# Subsheet_CAN.net
KiCad netlist of a schematic drawn in Altium Designer
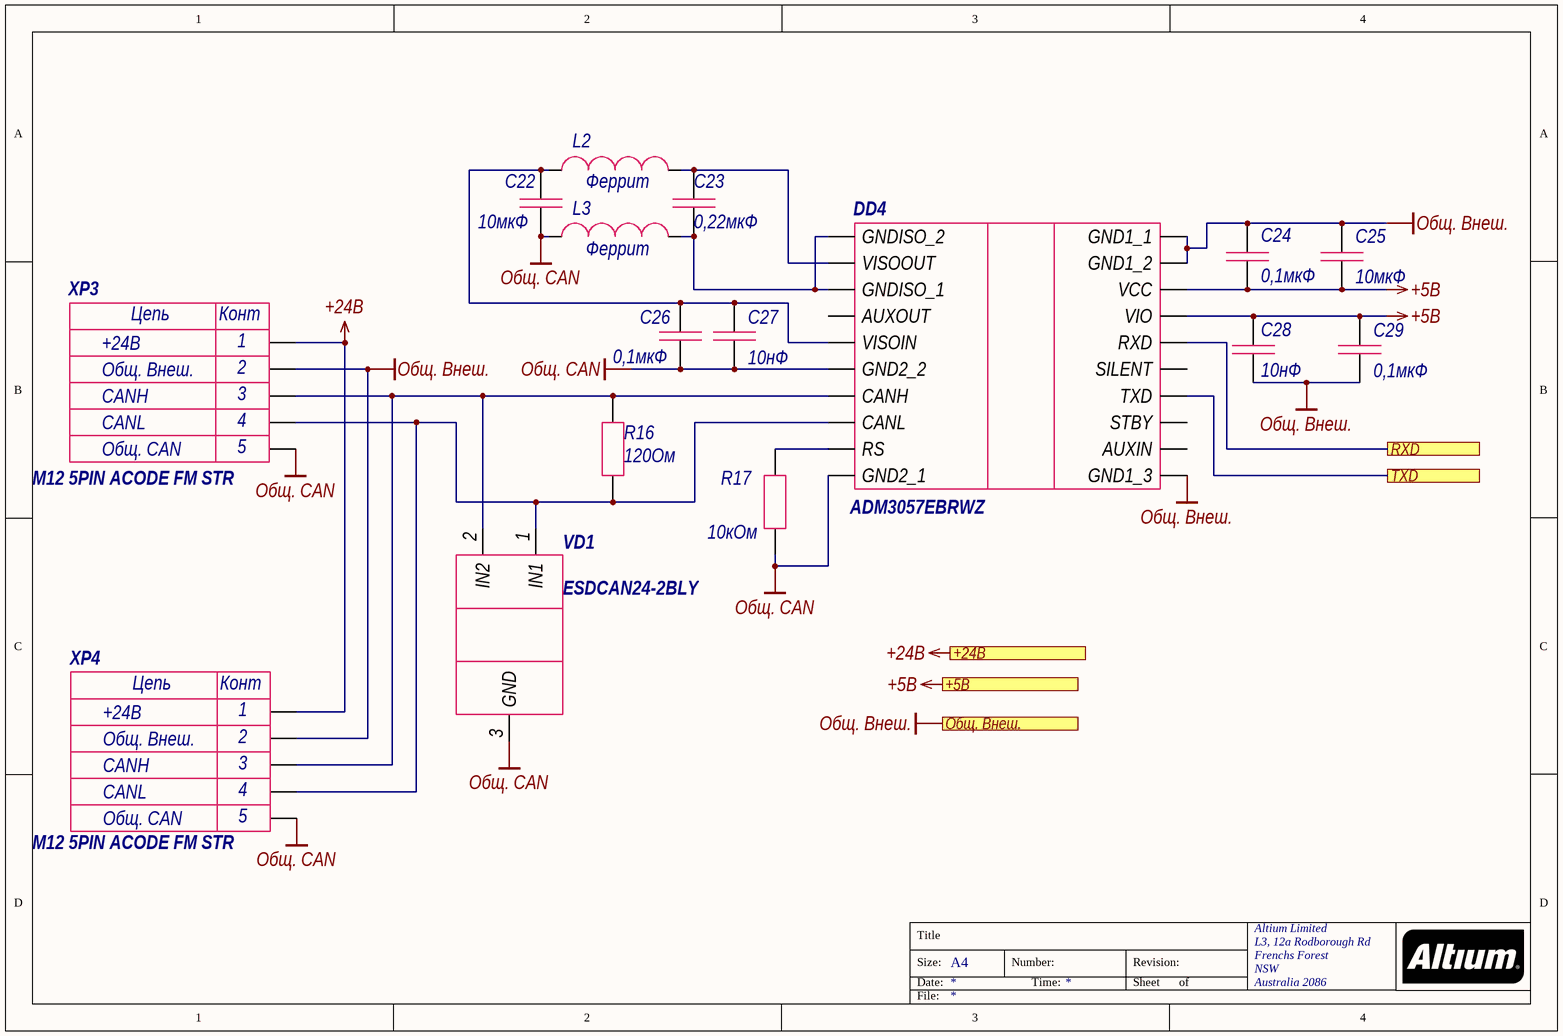
[diagram p0: Subsheet_CAN.SchDoc]

(export (version "E")
  (design (tool "Eeschema 10.0.6"))
  (components
    (comp (ref "C22")
      (value "10мкФ")
      (footprint "0805C")
      (fields (field (name "TOLERANCE") "10%") (field (name "Comment") "Capacitor"))
      (libsource (lib "Database_Maltsev") (part "Capacitor"))
    )
    (comp (ref "C23")
      (value "0,22мкФ")
      (footprint "0603C")
      (fields (field (name "TOLERANCE") "5%") (field (name "Comment") "Capacitor"))
      (libsource (lib "Database_Maltsev") (part "Capacitor"))
    )
    (comp (ref "C24")
      (value "0,1мкФ")
      (footprint "0603C")
      (fields (field (name "TOLERANCE") "10%") (field (name "Comment") "Capacitor"))
      (libsource (lib "Database_Maltsev") (part "Capacitor"))
    )
    (comp (ref "C25")
      (value "10мкФ")
      (footprint "0805C")
      (fields (field (name "TOLERANCE") "10%") (field (name "Comment") "Capacitor"))
      (libsource (lib "Database_Maltsev") (part "Capacitor"))
    )
    (comp (ref "C26")
      (value "0,1мкФ")
      (footprint "0603C")
      (fields (field (name "TOLERANCE") "10%") (field (name "Comment") "Capacitor"))
      (libsource (lib "Database_Maltsev") (part "Capacitor"))
    )
    (comp (ref "C27")
      (value "10нФ")
      (footprint "0603C")
      (fields (field (name "TOLERANCE") "10%") (field (name "Comment") "Capacitor"))
      (libsource (lib "Database_Maltsev") (part "Capacitor"))
    )
    (comp (ref "C28")
      (value "10нФ")
      (footprint "0603C")
      (fields (field (name "TOLERANCE") "10%") (field (name "Comment") "Capacitor"))
      (libsource (lib "Database_Maltsev") (part "Capacitor"))
    )
    (comp (ref "C29")
      (value "0,1мкФ")
      (footprint "0603C")
      (fields (field (name "TOLERANCE") "10%") (field (name "Comment") "Capacitor"))
      (libsource (lib "Database_Maltsev") (part "Capacitor"))
    )
    (comp (ref "DD4")
      (value "ADM3057EBRWZ")
      (footprint "SOIC-20N")
      (description "CAN")
      (libsource (lib "Database_Maltsev") (part "ADM3057EBRWZ"))
    )
    (comp (ref "L2")
      (value "Феррит")
      (footprint "0402")
      (fields (field (name "Comment") "Inductance"))
      (libsource (lib "Database_Maltsev") (part "Inductance"))
    )
    (comp (ref "L3")
      (value "Феррит")
      (footprint "0402")
      (fields (field (name "Comment") "Inductance"))
      (libsource (lib "Database_Maltsev") (part "Inductance"))
    )
    (comp (ref "R16")
      (value "120Ом")
      (footprint "0603R")
      (fields (field (name "TOLERANCE") "5%") (field (name "Comment") "Resistor"))
      (libsource (lib "Database_Maltsev") (part "Resistor"))
    )
    (comp (ref "R17")
      (value "10кОм")
      (footprint "0603R")
      (fields (field (name "TOLERANCE") "5%") (field (name "Comment") "Resistor"))
      (libsource (lib "Database_Maltsev") (part "Resistor"))
    )
    (comp (ref "VD1")
      (value "ESDCAN24-2BLY")
      (footprint "SOT23-3L")
      (description "TVS")
      (libsource (lib "Database_Maltsev") (part "ESDCAN24-2BLY"))
    )
    (comp (ref "XP3")
      (value "M12 5PIN ACODE FM STR")
      (footprint "M12_ACODE_5PIN_FM_STR")
      (description "A code ; Female ; Front mount")
      (fields
        (field (name "VALUE1") "+24В")
        (field (name "VALUE2") "Общ. Внеш.")
        (field (name "VALUE3") "CANH")
        (field (name "VALUE4") "CANL")
        (field (name "VALUE5") "Общ. CAN")
        (field (name "TOLERANCE") "straight")
        (field (name "Comment") "5_PIN_XP")
      )
      (libsource (lib "Database_Maltsev") (part "5_PIN_XP"))
    )
    (comp (ref "XP4")
      (value "M12 5PIN ACODE FM STR")
      (footprint "M12_ACODE_5PIN_FM_STR")
      (description "A code ; Female ; Front mount")
      (fields
        (field (name "VALUE1") "+24В")
        (field (name "VALUE2") "Общ. Внеш.")
        (field (name "VALUE3") "CANH")
        (field (name "VALUE4") "CANL")
        (field (name "VALUE5") "Общ. CAN")
        (field (name "TOLERANCE") "straight")
        (field (name "Comment") "5_PIN_XP")
      )
      (libsource (lib "Database_Maltsev") (part "5_PIN_XP"))
    )
  )
  (nets
    (net (code "1") (name "+5В") (class "Default")
      (node (ref "C24") (pin "1") (pinfunction "1_1") (pintype "passive"))
      (node (ref "C25") (pin "1") (pinfunction "1_1") (pintype "passive"))
      (node (ref "C28") (pin "2") (pinfunction "2_2") (pintype "passive"))
      (node (ref "C29") (pin "2") (pinfunction "2_2") (pintype "passive"))
      (node (ref "DD4") (pin "3") (pinfunction "VCC_3") (pintype "passive"))
      (node (ref "DD4") (pin "4") (pinfunction "VIO_4") (pintype "passive"))
    )
    (net (code "2") (name "+24В") (class "Default")
      (node (ref "XP3") (pin "1") (pinfunction "1_1") (pintype "passive"))
      (node (ref "XP4") (pin "1") (pinfunction "1_1") (pintype "passive"))
    )
    (net (code "3") (name "/RXD") (class "Default")
      (node (ref "DD4") (pin "5") (pinfunction "RXD_5") (pintype "passive"))
    )
    (net (code "4") (name "/TXD") (class "Default")
      (node (ref "DD4") (pin "7") (pinfunction "TXD_7") (pintype "passive"))
    )
    (net (code "5") (name "Net-(DD4-CANH)") (class "Default")
      (node (ref "DD4") (pin "14") (pinfunction "CANH_14") (pintype "passive"))
      (node (ref "R16") (pin "2") (pinfunction "2_2") (pintype "passive"))
      (node (ref "VD1") (pin "2") (pinfunction "IN2_2") (pintype "passive"))
      (node (ref "XP3") (pin "3") (pinfunction "3_3") (pintype "passive"))
      (node (ref "XP4") (pin "3") (pinfunction "3_3") (pintype "passive"))
    )
    (net (code "6") (name "Net-(DD4-CANL)") (class "Default")
      (node (ref "DD4") (pin "13") (pinfunction "CANL_13") (pintype "passive"))
      (node (ref "R16") (pin "1") (pinfunction "1_1") (pintype "passive"))
      (node (ref "VD1") (pin "1") (pinfunction "IN1_1") (pintype "passive"))
      (node (ref "XP3") (pin "4") (pinfunction "4_4") (pintype "passive"))
      (node (ref "XP4") (pin "4") (pinfunction "4_4") (pintype "passive"))
    )
    (net (code "7") (name "Net-(DD4-GNDISO_1)") (class "Default")
      (node (ref "C23") (pin "1") (pinfunction "1_1") (pintype "passive"))
      (node (ref "DD4") (pin "18") (pinfunction "GNDISO_1_18") (pintype "passive"))
      (node (ref "DD4") (pin "20") (pinfunction "GNDISO_2_20") (pintype "passive"))
      (node (ref "L3") (pin "2") (pinfunction "2_2") (pintype "passive"))
    )
    (net (code "8") (name "Net-(DD4-RS)") (class "Default")
      (node (ref "DD4") (pin "12") (pinfunction "RS_12") (pintype "passive"))
      (node (ref "R17") (pin "2") (pinfunction "2_2") (pintype "passive"))
    )
    (net (code "9") (name "Net-(DD4-VISOIN)") (class "Default")
      (node (ref "C22") (pin "2") (pinfunction "2_2") (pintype "passive"))
      (node (ref "C26") (pin "2") (pinfunction "2_2") (pintype "passive"))
      (node (ref "C27") (pin "2") (pinfunction "2_2") (pintype "passive"))
      (node (ref "DD4") (pin "16") (pinfunction "VISOIN_16") (pintype "passive"))
      (node (ref "L2") (pin "1") (pinfunction "1_1") (pintype "passive"))
    )
    (net (code "10") (name "Net-(DD4-VISOOUT)") (class "Default")
      (node (ref "C23") (pin "2") (pinfunction "2_2") (pintype "passive"))
      (node (ref "DD4") (pin "19") (pinfunction "VISOOUT_19") (pintype "passive"))
      (node (ref "L2") (pin "2") (pinfunction "2_2") (pintype "passive"))
    )
    (net (code "11") (name "unconnected-(DD4-AUXIN-Pad9)") (class "Default")
      (node (ref "DD4") (pin "9") (pinfunction "AUXIN_9") (pintype "passive"))
    )
    (net (code "12") (name "unconnected-(DD4-AUXOUT-Pad17)") (class "Default")
      (node (ref "DD4") (pin "17") (pinfunction "AUXOUT_17") (pintype "passive"))
    )
    (net (code "13") (name "unconnected-(DD4-SILENT-Pad6)") (class "Default")
      (node (ref "DD4") (pin "6") (pinfunction "SILENT_6") (pintype "passive"))
    )
    (net (code "14") (name "unconnected-(DD4-STBY-Pad8)") (class "Default")
      (node (ref "DD4") (pin "8") (pinfunction "STBY_8") (pintype "passive"))
    )
    (net (code "15") (name "Общ. CAN") (class "Default")
      (node (ref "C22") (pin "1") (pinfunction "1_1") (pintype "passive"))
      (node (ref "C26") (pin "1") (pinfunction "1_1") (pintype "passive"))
      (node (ref "C27") (pin "1") (pinfunction "1_1") (pintype "passive"))
      (node (ref "DD4") (pin "11") (pinfunction "GND2_1_11") (pintype "passive"))
      (node (ref "DD4") (pin "15") (pinfunction "GND2_2_15") (pintype "passive"))
      (node (ref "L3") (pin "1") (pinfunction "1_1") (pintype "passive"))
      (node (ref "R17") (pin "1") (pinfunction "1_1") (pintype "passive"))
      (node (ref "VD1") (pin "3") (pinfunction "GND_3") (pintype "passive"))
      (node (ref "XP3") (pin "5") (pinfunction "5_5") (pintype "passive"))
      (node (ref "XP4") (pin "5") (pinfunction "5_5") (pintype "passive"))
    )
    (net (code "16") (name "Общ. Внеш.") (class "Default")
      (node (ref "C24") (pin "2") (pinfunction "2_2") (pintype "passive"))
      (node (ref "C25") (pin "2") (pinfunction "2_2") (pintype "passive"))
      (node (ref "C28") (pin "1") (pinfunction "1_1") (pintype "passive"))
      (node (ref "C29") (pin "1") (pinfunction "1_1") (pintype "passive"))
      (node (ref "DD4") (pin "1") (pinfunction "GND1_1_1") (pintype "passive"))
      (node (ref "DD4") (pin "10") (pinfunction "GND1_3_10") (pintype "passive"))
      (node (ref "DD4") (pin "2") (pinfunction "GND1_2_2") (pintype "passive"))
      (node (ref "XP3") (pin "2") (pinfunction "2_2") (pintype "passive"))
      (node (ref "XP4") (pin "2") (pinfunction "2_2") (pintype "passive"))
    )
  )
)
